# sdram-16-bit.net
KiCad netlist of a schematic drawn in Altium Designer
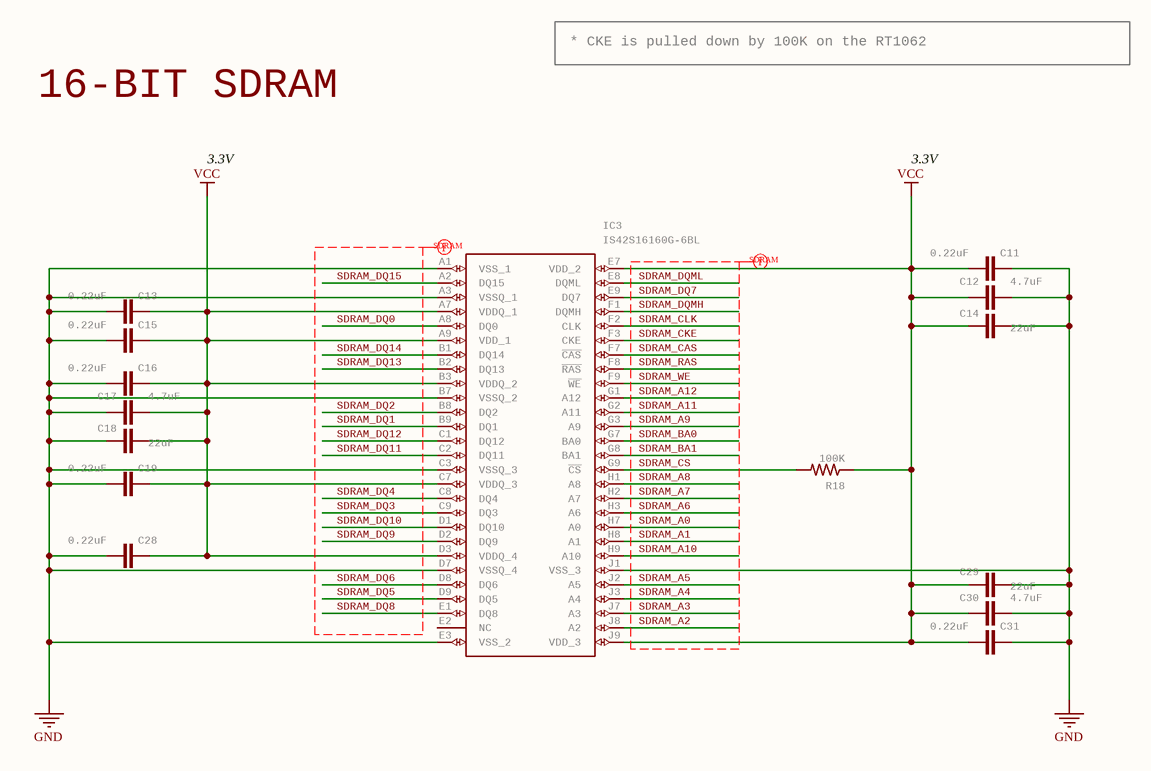
[diagram p0: sdram-16-bit.SchDoc]

(export (version "E")
  (design (tool "Eeschema 10.0.6"))
  (components
    (comp (ref "C11")
      (value "0.22uF")
      (footprint "C0201")
      (description "CAPACITOR, European symbol")
      (fields (field (name "MPN") "GRM033R60J224ME15D"))
      (libsource (lib "rt10") (part "C-EUC0201"))
    )
    (comp (ref "C12")
      (value "4.7uF")
      (footprint "0402-CAP")
      (description "CapacitorStandard 0603 ceramic capacitor, and 0.1\" leaded capacitor.")
      (fields (field (name "MPN") "JMK105BBJ475MV-F"))
      (libsource (lib "rt10") (part "CAP0402-CAP"))
    )
    (comp (ref "C13")
      (value "0.22uF")
      (footprint "C0201")
      (description "CAPACITOR, European symbol")
      (fields (field (name "MPN") "GRM033R60J224ME15D"))
      (libsource (lib "rt10") (part "C-EUC0201"))
    )
    (comp (ref "C14")
      (value "22uF")
      (footprint "0805")
      (fields (field (name "MPN") "CL21A226MQQNNNE"))
      (libsource (lib "rt10") (part "22UF-0805-6.3V-20%"))
    )
    (comp (ref "C15")
      (value "0.22uF")
      (footprint "C0201")
      (description "CAPACITOR, European symbol")
      (fields (field (name "MPN") "GRM033R60J224ME15D"))
      (libsource (lib "rt10") (part "C-EUC0201"))
    )
    (comp (ref "C16")
      (value "0.22uF")
      (footprint "C0201")
      (description "CAPACITOR, European symbol")
      (fields (field (name "MPN") "GRM033R60J224ME15D"))
      (libsource (lib "rt10") (part "C-EUC0201"))
    )
    (comp (ref "C17")
      (value "4.7uF")
      (footprint "0402-CAP")
      (description "CapacitorStandard 0603 ceramic capacitor, and 0.1\" leaded capacitor.")
      (fields (field (name "MPN") "JMK105BBJ475MV-F"))
      (libsource (lib "rt10") (part "CAP0402-CAP"))
    )
    (comp (ref "C18")
      (value "22uF")
      (footprint "0805")
      (fields (field (name "MPN") "CL21A226MQQNNNE"))
      (libsource (lib "rt10") (part "22UF-0805-6.3V-20%"))
    )
    (comp (ref "C19")
      (value "0.22uF")
      (footprint "C0201")
      (description "CAPACITOR, European symbol")
      (fields (field (name "MPN") "GRM033R60J224ME15D"))
      (libsource (lib "rt10") (part "C-EUC0201"))
    )
    (comp (ref "C28")
      (value "0.22uF")
      (footprint "C0201")
      (description "CAPACITOR, European symbol")
      (fields (field (name "MPN") "GRM033R60J224ME15D"))
      (libsource (lib "rt10") (part "C-EUC0201"))
    )
    (comp (ref "C29")
      (value "22uF")
      (footprint "0805")
      (fields (field (name "MPN") "CL21A226MQQNNNE"))
      (libsource (lib "rt10") (part "22UF-0805-6.3V-20%"))
    )
    (comp (ref "C30")
      (value "4.7uF")
      (footprint "0402-CAP")
      (description "CapacitorStandard 0603 ceramic capacitor, and 0.1\" leaded capacitor.")
      (fields (field (name "MPN") "JMK105BBJ475MV-F"))
      (libsource (lib "rt10") (part "CAP0402-CAP"))
    )
    (comp (ref "C31")
      (value "0.22uF")
      (footprint "C0201")
      (description "CAPACITOR, European symbol")
      (fields (field (name "MPN") "GRM033R60J224ME15D"))
      (libsource (lib "rt10") (part "C-EUC0201"))
    )
    (comp (ref "IC3")
      (value "IS42S16160G-6BL")
      (footprint "BGA54C80P9X9_800X800X120")
      (description "DRAM 256M 16Mx16 166Mhz SDR SDRAM, 3.3V   Source:  Datasheet")
      (fields (field (name "MOUSER_PART_NUMBER") "870-IS42S16160G-6BL"))
      (libsource (lib "rt10") (part "IS42S16160G-6BL"))
    )
    (comp (ref "R18")
      (value "100K")
      (footprint "0402-RES")
      (description "ResistorBasic schematic elements and footprints for 0603, 1206, and PTH resistors.")
      (fields (field (name "MPN") "AC0402FR-07100KL"))
      (libsource (lib "rt10") (part "RESISTOR0402-RES"))
    )
  )
  (nets
    (net (code "1") (name "/SDRAM_A0") (class "Default")
      (node (ref "IC3") (pin "H7") (pinfunction "A0_H7") (pintype "bidirectional"))
    )
    (net (code "2") (name "/SDRAM_A1") (class "Default")
      (node (ref "IC3") (pin "H8") (pinfunction "A1_H8") (pintype "bidirectional"))
    )
    (net (code "3") (name "/SDRAM_A2") (class "Default")
      (node (ref "IC3") (pin "J8") (pinfunction "A2_J8") (pintype "bidirectional"))
    )
    (net (code "4") (name "/SDRAM_A3") (class "Default")
      (node (ref "IC3") (pin "J7") (pinfunction "A3_J7") (pintype "bidirectional"))
    )
    (net (code "5") (name "/SDRAM_A4") (class "Default")
      (node (ref "IC3") (pin "J3") (pinfunction "A4_J3") (pintype "bidirectional"))
    )
    (net (code "6") (name "/SDRAM_A5") (class "Default")
      (node (ref "IC3") (pin "J2") (pinfunction "A5_J2") (pintype "bidirectional"))
    )
    (net (code "7") (name "/SDRAM_A6") (class "Default")
      (node (ref "IC3") (pin "H3") (pinfunction "A6_H3") (pintype "bidirectional"))
    )
    (net (code "8") (name "/SDRAM_A7") (class "Default")
      (node (ref "IC3") (pin "H2") (pinfunction "A7_H2") (pintype "bidirectional"))
    )
    (net (code "9") (name "/SDRAM_A8") (class "Default")
      (node (ref "IC3") (pin "H1") (pinfunction "A8_H1") (pintype "bidirectional"))
    )
    (net (code "10") (name "/SDRAM_A9") (class "Default")
      (node (ref "IC3") (pin "G3") (pinfunction "A9_G3") (pintype "bidirectional"))
    )
    (net (code "11") (name "/SDRAM_A10") (class "Default")
      (node (ref "IC3") (pin "H9") (pinfunction "A10_H9") (pintype "bidirectional"))
    )
    (net (code "12") (name "/SDRAM_A11") (class "Default")
      (node (ref "IC3") (pin "G2") (pinfunction "A11_G2") (pintype "bidirectional"))
    )
    (net (code "13") (name "/SDRAM_A12") (class "Default")
      (node (ref "IC3") (pin "G1") (pinfunction "A12_G1") (pintype "bidirectional"))
    )
    (net (code "14") (name "/SDRAM_BA0") (class "Default")
      (node (ref "IC3") (pin "G7") (pinfunction "BA0_G7") (pintype "bidirectional"))
    )
    (net (code "15") (name "/SDRAM_BA1") (class "Default")
      (node (ref "IC3") (pin "G8") (pinfunction "BA1_G8") (pintype "bidirectional"))
    )
    (net (code "16") (name "/SDRAM_CAS") (class "Default")
      (node (ref "IC3") (pin "F7") (pinfunction "~{CAS}_F7") (pintype "bidirectional"))
    )
    (net (code "17") (name "/SDRAM_CKE") (class "Default")
      (node (ref "IC3") (pin "F3") (pinfunction "CKE_F3") (pintype "bidirectional"))
    )
    (net (code "18") (name "/SDRAM_CLK") (class "Default")
      (node (ref "IC3") (pin "F2") (pinfunction "CLK_F2") (pintype "bidirectional"))
    )
    (net (code "19") (name "/SDRAM_CS") (class "Default")
      (node (ref "IC3") (pin "G9") (pinfunction "~{CS}_G9") (pintype "bidirectional"))
      (node (ref "R18") (pin "2") (pinfunction "2_2") (pintype "passive"))
    )
    (net (code "20") (name "/SDRAM_DQ0") (class "Default")
      (node (ref "IC3") (pin "A8") (pinfunction "DQ0_A8") (pintype "bidirectional"))
    )
    (net (code "21") (name "/SDRAM_DQ1") (class "Default")
      (node (ref "IC3") (pin "B9") (pinfunction "DQ1_B9") (pintype "bidirectional"))
    )
    (net (code "22") (name "/SDRAM_DQ2") (class "Default")
      (node (ref "IC3") (pin "B8") (pinfunction "DQ2_B8") (pintype "bidirectional"))
    )
    (net (code "23") (name "/SDRAM_DQ3") (class "Default")
      (node (ref "IC3") (pin "C9") (pinfunction "DQ3_C9") (pintype "bidirectional"))
    )
    (net (code "24") (name "/SDRAM_DQ4") (class "Default")
      (node (ref "IC3") (pin "C8") (pinfunction "DQ4_C8") (pintype "bidirectional"))
    )
    (net (code "25") (name "/SDRAM_DQ5") (class "Default")
      (node (ref "IC3") (pin "D9") (pinfunction "DQ5_D9") (pintype "bidirectional"))
    )
    (net (code "26") (name "/SDRAM_DQ6") (class "Default")
      (node (ref "IC3") (pin "D8") (pinfunction "DQ6_D8") (pintype "bidirectional"))
    )
    (net (code "27") (name "/SDRAM_DQ7") (class "Default")
      (node (ref "IC3") (pin "E9") (pinfunction "DQ7_E9") (pintype "bidirectional"))
    )
    (net (code "28") (name "/SDRAM_DQ8") (class "Default")
      (node (ref "IC3") (pin "E1") (pinfunction "DQ8_E1") (pintype "bidirectional"))
    )
    (net (code "29") (name "/SDRAM_DQ9") (class "Default")
      (node (ref "IC3") (pin "D2") (pinfunction "DQ9_D2") (pintype "bidirectional"))
    )
    (net (code "30") (name "/SDRAM_DQ10") (class "Default")
      (node (ref "IC3") (pin "D1") (pinfunction "DQ10_D1") (pintype "bidirectional"))
    )
    (net (code "31") (name "/SDRAM_DQ11") (class "Default")
      (node (ref "IC3") (pin "C2") (pinfunction "DQ11_C2") (pintype "bidirectional"))
    )
    (net (code "32") (name "/SDRAM_DQ12") (class "Default")
      (node (ref "IC3") (pin "C1") (pinfunction "DQ12_C1") (pintype "bidirectional"))
    )
    (net (code "33") (name "/SDRAM_DQ13") (class "Default")
      (node (ref "IC3") (pin "B2") (pinfunction "DQ13_B2") (pintype "bidirectional"))
    )
    (net (code "34") (name "/SDRAM_DQ14") (class "Default")
      (node (ref "IC3") (pin "B1") (pinfunction "DQ14_B1") (pintype "bidirectional"))
    )
    (net (code "35") (name "/SDRAM_DQ15") (class "Default")
      (node (ref "IC3") (pin "A2") (pinfunction "DQ15_A2") (pintype "bidirectional"))
    )
    (net (code "36") (name "/SDRAM_DQMH") (class "Default")
      (node (ref "IC3") (pin "F1") (pinfunction "DQMH_F1") (pintype "bidirectional"))
    )
    (net (code "37") (name "/SDRAM_DQML") (class "Default")
      (node (ref "IC3") (pin "E8") (pinfunction "DQML_E8") (pintype "bidirectional"))
    )
    (net (code "38") (name "/SDRAM_RAS") (class "Default")
      (node (ref "IC3") (pin "F8") (pinfunction "~{RAS}_F8") (pintype "bidirectional"))
    )
    (net (code "39") (name "/SDRAM_WE") (class "Default")
      (node (ref "IC3") (pin "F9") (pinfunction "~{WE}_F9") (pintype "bidirectional"))
    )
    (net (code "40") (name "GND") (class "Default")
      (node (ref "C11") (pin "1") (pinfunction "1_1") (pintype "passive"))
      (node (ref "C12") (pin "2") (pinfunction "2_2") (pintype "passive"))
      (node (ref "C13") (pin "2") (pinfunction "2_2") (pintype "passive"))
      (node (ref "C14") (pin "2") (pinfunction "2_2") (pintype "passive"))
      (node (ref "C15") (pin "2") (pinfunction "2_2") (pintype "passive"))
      (node (ref "C16") (pin "2") (pinfunction "2_2") (pintype "passive"))
      (node (ref "C17") (pin "1") (pinfunction "1_1") (pintype "passive"))
      (node (ref "C18") (pin "1") (pinfunction "1_1") (pintype "passive"))
      (node (ref "C19") (pin "2") (pinfunction "2_2") (pintype "passive"))
      (node (ref "C28") (pin "2") (pinfunction "2_2") (pintype "passive"))
      (node (ref "C29") (pin "2") (pinfunction "2_2") (pintype "passive"))
      (node (ref "C30") (pin "2") (pinfunction "2_2") (pintype "passive"))
      (node (ref "C31") (pin "1") (pinfunction "1_1") (pintype "passive"))
      (node (ref "IC3") (pin "A1") (pinfunction "VSS_1_A1") (pintype "bidirectional"))
      (node (ref "IC3") (pin "A3") (pinfunction "VSSQ_1_A3") (pintype "bidirectional"))
      (node (ref "IC3") (pin "B7") (pinfunction "VSSQ_2_B7") (pintype "bidirectional"))
      (node (ref "IC3") (pin "C3") (pinfunction "VSSQ_3_C3") (pintype "bidirectional"))
      (node (ref "IC3") (pin "D7") (pinfunction "VSSQ_4_D7") (pintype "bidirectional"))
      (node (ref "IC3") (pin "E3") (pinfunction "VSS_2_E3") (pintype "bidirectional"))
      (node (ref "IC3") (pin "J1") (pinfunction "VSS_3_J1") (pintype "bidirectional"))
    )
    (net (code "41") (name "VCC") (class "Default")
      (node (ref "C11") (pin "2") (pinfunction "2_2") (pintype "passive"))
      (node (ref "C12") (pin "1") (pinfunction "1_1") (pintype "passive"))
      (node (ref "C13") (pin "1") (pinfunction "1_1") (pintype "passive"))
      (node (ref "C14") (pin "1") (pinfunction "1_1") (pintype "passive"))
      (node (ref "C15") (pin "1") (pinfunction "1_1") (pintype "passive"))
      (node (ref "C16") (pin "1") (pinfunction "1_1") (pintype "passive"))
      (node (ref "C17") (pin "2") (pinfunction "2_2") (pintype "passive"))
      (node (ref "C18") (pin "2") (pinfunction "2_2") (pintype "passive"))
      (node (ref "C19") (pin "1") (pinfunction "1_1") (pintype "passive"))
      (node (ref "C28") (pin "1") (pinfunction "1_1") (pintype "passive"))
      (node (ref "C29") (pin "1") (pinfunction "1_1") (pintype "passive"))
      (node (ref "C30") (pin "1") (pinfunction "1_1") (pintype "passive"))
      (node (ref "C31") (pin "2") (pinfunction "2_2") (pintype "passive"))
      (node (ref "IC3") (pin "A7") (pinfunction "VDDQ_1_A7") (pintype "bidirectional"))
      (node (ref "IC3") (pin "A9") (pinfunction "VDD_1_A9") (pintype "bidirectional"))
      (node (ref "IC3") (pin "B3") (pinfunction "VDDQ_2_B3") (pintype "bidirectional"))
      (node (ref "IC3") (pin "C7") (pinfunction "VDDQ_3_C7") (pintype "bidirectional"))
      (node (ref "IC3") (pin "D3") (pinfunction "VDDQ_4_D3") (pintype "bidirectional"))
      (node (ref "IC3") (pin "E7") (pinfunction "VDD_2_E7") (pintype "bidirectional"))
      (node (ref "IC3") (pin "J9") (pinfunction "VDD_3_J9") (pintype "bidirectional"))
      (node (ref "R18") (pin "1") (pinfunction "1_1") (pintype "passive"))
    )
    (net (code "42") (name "unconnected-(IC3-NC-PadE2)") (class "Default")
      (node (ref "IC3") (pin "E2") (pinfunction "NC_E2") (pintype "passive"))
    )
  )
)
